# AlarmRelay.net
KiCad netlist of a schematic drawn in Altium Designer
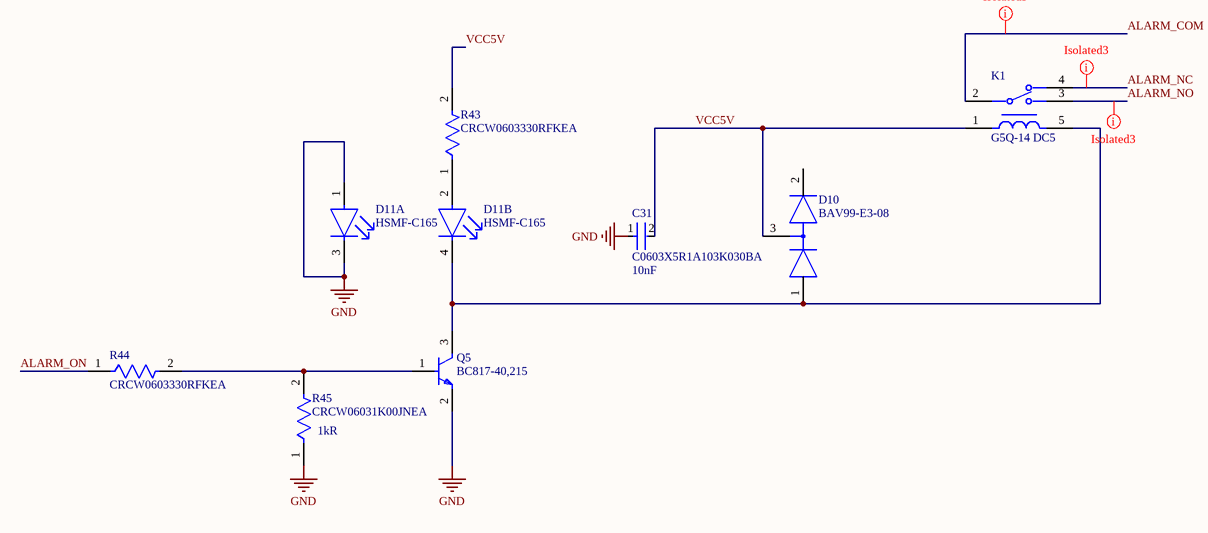
[diagram p0: AlarmRelay.SchDoc]

(export (version "E")
  (design (tool "Eeschema 10.0.6"))
  (components
    (comp (ref "C31")
      (value "C0603X5R1A103K030BA")
      (footprint "FP-C0603-030-0_03-MFG")
      (description "Multilayer Ceramic Capacitors 10nF ±10% 10V X5R SMD 0201")
      (fields
        (field (name "CAPACITANCE") "10nF")
        (field (name "TOLERANCE") "10%")
        (field (name "VOLTAGE") "10V")
      )
      (libsource (lib "Altium Content Vault") (part "02cd4be3c70576c341d710602a673aa"))
    )
    (comp (ref "D10")
      (value "BAV99-E3-08")
      (footprint "FP-6_541-5014_01-4-MFG")
      (description "DIODE ARRAY GP 70V 150MA SOT23")
      (fields
        (field (name "OCTOPART") "https://octopart.com/bav99-e3-08-vishay-46456629")
        (field (name "MANUFACTURER") "Vishay")
      )
      (libsource (lib "Altium Content Vault") (part "5a70a177f81bbb88f7262b7de8d09a0"))
    )
    (comp (ref "D11")
      (value "HSMF-C165")
      (footprint "FP-HSMF-C165-MFG")
      (description "LED GREEN/RED DIFFUSED 0603 SMD")
      (libsource (lib "Altium Content Vault") (part "7c1fe340d8ce6b5db8c50b7ec3493de"))
    )
    (comp (ref "K1")
      (value "G5Q-14 DC5")
      (footprint "FP-G5Q-14_DC5-MFG")
      (description "RELAY GEN PURPOSE SPDT 10A 5V")
      (fields
        (field (name "OCTOPART") "https://octopart.com/g5q-14+dc5-omron-71281")
        (field (name "MANUFACTURER") "Omron")
      )
      (libsource (lib "Altium Content Vault") (part "09d7468cc7bd4f4e7a2ff62bdae3adb"))
    )
    (comp (ref "Q5")
      (value "BC817-40,215")
      (footprint "FP-SOT23-MFG")
      (description "TRANS NPN 45V 0.5A SOT23")
      (fields
        (field (name "OCTOPART") "https://octopart.com/bc817-40%2C215-nexperia-78739081")
        (field (name "MANUFACTURER") "Nexperia")
      )
      (libsource (lib "Altium Content Vault") (part "b44e953556f554d0102664c7d152cb4"))
    )
    (comp (ref "R43")
      (value "CRCW0603330RFKEA")
      (footprint "FP-CRCW0603-e3-MFG")
      (description "RES Thick Film, 330Ω, 1%, 0.1W, 100ppm/°C, 0603")
      (fields (field (name "TOLERANCE") "1%"))
      (libsource (lib "Altium Content Vault") (part "1029c3af85768c4190bb7ad29bc67b5"))
    )
    (comp (ref "R44")
      (value "CRCW0603330RFKEA")
      (footprint "FP-CRCW0603-e3-MFG")
      (description "RES Thick Film, 330Ω, 1%, 0.1W, 100ppm/°C, 0603")
      (fields (field (name "TOLERANCE") "1%"))
      (libsource (lib "Altium Content Vault") (part "1029c3af85768c4190bb7ad29bc67b5"))
    )
    (comp (ref "R45")
      (value "CRCW06031K00JNEA")
      (footprint "FP-CRCW0603-e3-IPC_C")
      (description "RES Thick Film, 1kΩ, 5%, 0.1W, 200ppm/°C, 0603")
      (fields (field (name "TOLERANCE") "5%") (field (name "RESISTANCE") "1kR"))
      (libsource (lib "Altium Content Vault") (part "1029c3af85768c4190bb7ad29bc67b5"))
    )
  )
  (nets
    (net (code "1") (name "/ALARM_COM") (class "Default")
      (node (ref "K1") (pin "2") (pinfunction "2_2") (pintype "passive"))
    )
    (net (code "2") (name "/ALARM_NC") (class "Default")
      (node (ref "K1") (pin "4") (pinfunction "4_4") (pintype "passive"))
    )
    (net (code "3") (name "/ALARM_NO") (class "Default")
      (node (ref "K1") (pin "3") (pinfunction "3_3") (pintype "passive"))
    )
    (net (code "4") (name "/ALARM_ON") (class "Default")
      (node (ref "R44") (pin "1") (pinfunction "1_1") (pintype "passive"))
    )
    (net (code "5") (name "/VCC5V") (class "Default")
      (node (ref "C31") (pin "2") (pinfunction "2_2") (pintype "passive"))
      (node (ref "D10") (pin "3") (pinfunction "3_3") (pintype "passive"))
      (node (ref "K1") (pin "1") (pinfunction "1_1") (pintype "passive"))
      (node (ref "R43") (pin "2") (pinfunction "2_2") (pintype "passive"))
    )
    (net (code "6") (name "GND") (class "Default")
      (node (ref "C31") (pin "1") (pinfunction "1_1") (pintype "passive"))
      (node (ref "D11") (pin "1") (pinfunction "GREEN_A_1") (pintype "passive"))
      (node (ref "D11") (pin "3") (pinfunction "GREEN_C_3") (pintype "passive"))
      (node (ref "Q5") (pin "2") (pinfunction "E_2") (pintype "passive"))
      (node (ref "R45") (pin "1") (pinfunction "1_1") (pintype "passive"))
    )
    (net (code "7") (name "Net-(D11B-RED_A)") (class "Default")
      (node (ref "D11") (pin "2") (pinfunction "RED_A_2") (pintype "passive"))
      (node (ref "R43") (pin "1") (pinfunction "1_1") (pintype "passive"))
    )
    (net (code "8") (name "Net-(D11B-RED_C)") (class "Default")
      (node (ref "D10") (pin "1") (pinfunction "1_1") (pintype "passive"))
      (node (ref "D11") (pin "4") (pinfunction "RED_C_4") (pintype "passive"))
      (node (ref "K1") (pin "5") (pinfunction "5_5") (pintype "passive"))
      (node (ref "Q5") (pin "3") (pinfunction "C_3") (pintype "passive"))
    )
    (net (code "9") (name "Net-(Q5-B)") (class "Default")
      (node (ref "Q5") (pin "1") (pinfunction "B_1") (pintype "passive"))
      (node (ref "R44") (pin "2") (pinfunction "2_2") (pintype "passive"))
      (node (ref "R45") (pin "2") (pinfunction "2_2") (pintype "passive"))
    )
    (net (code "10") (name "unconnected-(D10-Pad2)") (class "Default")
      (node (ref "D10") (pin "2") (pinfunction "2_2") (pintype "passive"))
    )
  )
)
